# nfc-epd-power.net
KiCad netlist of a schematic drawn in Altium Designer
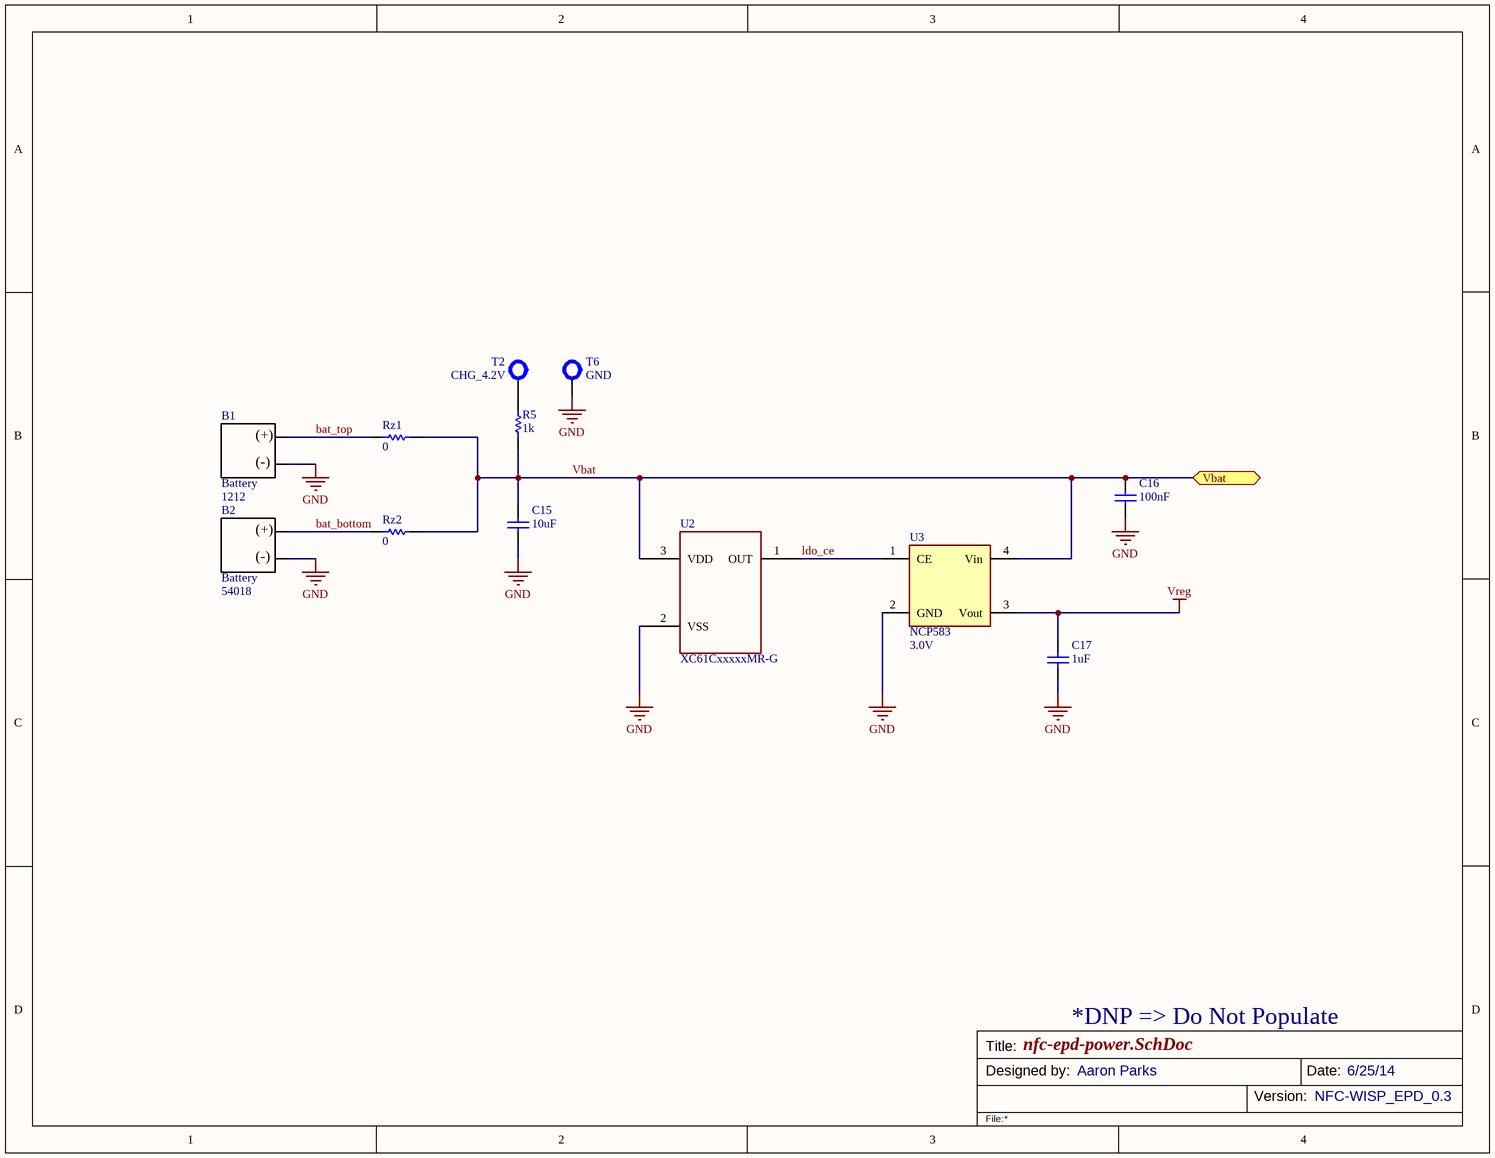
[diagram p0: nfc-epd-power.SchDoc]

(export (version "E")
  (design (tool "Eeschema 10.0.6"))
  (components
    (comp (ref "B1")
      (value "Battery")
      (footprint "PGEB0121212")
      (description "Powerstream Lithium Battery")
      (fields (field (name "NOTE") "1212"))
      (libsource (lib "powerstream") (part "Powerstream_Battery"))
    )
    (comp (ref "B2")
      (value "Battery")
      (footprint "PGEB0054018")
      (description "Powerstream Lithium Battery")
      (fields (field (name "NOTE") "54018"))
      (libsource (lib "powerstream") (part "Powerstream_Battery"))
    )
    (comp (ref "C15")
      (value "10uF")
      (footprint "0603")
      (description "Ceramic Capacitor (Surface Mount)")
      (fields (field (name "MANUFACTURER") "Generic Ceramic Chip Cap (TBD)") (field (name "Comment") "Cap"))
      (libsource (lib "WISP_AD10") (part "Cap"))
    )
    (comp (ref "C16")
      (value "100nF")
      (footprint "0402")
      (description "Ceramic Capacitor (Surface Mount)")
      (fields (field (name "MANUFACTURER") "Generic Ceramic Chip Cap (TBD)") (field (name "Comment") "Cap"))
      (libsource (lib "WISP_AD10") (part "Cap"))
    )
    (comp (ref "C17")
      (value "1uF")
      (footprint "0402")
      (description "Ceramic Capacitor (Surface Mount)")
      (fields (field (name "MANUFACTURER") "Generic Ceramic Chip Cap (TBD)") (field (name "Comment") "Cap"))
      (libsource (lib "WISP_AD10") (part "Cap"))
    )
    (comp (ref "R5")
      (value "1k")
      (footprint "0402")
      (description "Chip Resistor (Surface Mount)")
      (fields (field (name "MANUFACTURER") "Generic Chip Res (TBD)") (field (name "Comment") "Res"))
      (libsource (lib "WISP_AD10") (part "Res"))
    )
    (comp (ref "Rz1")
      (value "0")
      (footprint "0402")
      (description "Chip Resistor (Surface Mount)")
      (fields (field (name "MANUFACTURER") "Generic Chip Res (TBD)") (field (name "Comment") "Res"))
      (libsource (lib "WISP_AD10") (part "Res"))
    )
    (comp (ref "Rz2")
      (value "0")
      (footprint "0402")
      (description "Chip Resistor (Surface Mount)")
      (fields (field (name "MANUFACTURER") "Generic Chip Res (TBD)") (field (name "Comment") "Res"))
      (libsource (lib "WISP_AD10") (part "Res"))
    )
    (comp (ref "T2")
      (value "Test Point")
      (footprint "Test Point - Small")
      (description "Test Point, large or small foot prints")
      (fields
        (field (name "DIGI-KEY PART NUMBER") "Example: 5000K-ND, 5012K-ND, Surface mount 5015KCT-ND")
        (field (name "MANUFACTURER PART NUMBER") "Example: 5000, 5013")
        (field (name "NOTE") "CHG_4.2V")
      )
      (libsource (lib "WISP_AD10") (part "Test Point"))
    )
    (comp (ref "T6")
      (value "Test Point")
      (footprint "Test Point - Small")
      (description "Test Point, large or small foot prints")
      (fields
        (field (name "DIGI-KEY PART NUMBER") "Example: 5000K-ND, 5012K-ND, Surface mount 5015KCT-ND")
        (field (name "MANUFACTURER PART NUMBER") "Example: 5000, 5013")
        (field (name "NOTE") "GND")
      )
      (libsource (lib "WISP_AD10") (part "Test Point"))
    )
    (comp (ref "U2")
      (value "XC61CxxxxxMR-G")
      (footprint "SOT23 - N")
      (description "Torex IC Supervisor, SOT-23")
      (libsource (lib "WISP_AD10") (part "XC61CxxxxxMR-G"))
    )
    (comp (ref "U3")
      (value "NCP583")
      (footprint "SC82-AB")
      (description "Regulator: Ultra-Low Iq 150mA CMOS LDO Regulator with Enable")
      (fields
        (field (name "DIGI-KEY PART NUMBER") "NCP583SQ18T1GOSCT-ND")
        (field (name "MANUFACTURER") "ON Semiconductor")
        (field (name "ALTIUM_VALUE") "3.0V")
      )
      (libsource (lib "WISP_AD10") (part "NCP583"))
    )
  )
  (nets
    (net (code "1") (name "/Vbat") (class "Default")
      (node (ref "C15") (pin "2") (pinfunction "2_2") (pintype "passive"))
      (node (ref "C16") (pin "2") (pinfunction "2_2") (pintype "passive"))
      (node (ref "R5") (pin "1") (pinfunction "1_1") (pintype "passive"))
      (node (ref "Rz1") (pin "1") (pinfunction "1_1") (pintype "passive"))
      (node (ref "Rz2") (pin "1") (pinfunction "1_1") (pintype "passive"))
      (node (ref "U2") (pin "3") (pinfunction "VDD_3") (pintype "passive"))
      (node (ref "U3") (pin "4") (pinfunction "Vin_4") (pintype "passive"))
    )
    (net (code "2") (name "/bat_bottom") (class "Default")
      (node (ref "B2") (pin "2") (pinfunction "BAT_POS_2") (pintype "passive"))
      (node (ref "Rz2") (pin "2") (pinfunction "2_2") (pintype "passive"))
    )
    (net (code "3") (name "/bat_top") (class "Default")
      (node (ref "B1") (pin "2") (pinfunction "BAT_POS_2") (pintype "passive"))
      (node (ref "Rz1") (pin "2") (pinfunction "2_2") (pintype "passive"))
    )
    (net (code "4") (name "/ldo_ce") (class "Default")
      (node (ref "U2") (pin "1") (pinfunction "OUT_1") (pintype "passive"))
      (node (ref "U3") (pin "1") (pinfunction "CE_1") (pintype "passive"))
    )
    (net (code "5") (name "GND") (class "Default")
      (node (ref "B1") (pin "1") (pinfunction "BAT_NEG_1") (pintype "passive"))
      (node (ref "B2") (pin "1") (pinfunction "BAT_NEG_1") (pintype "passive"))
      (node (ref "C15") (pin "1") (pinfunction "1_1") (pintype "passive"))
      (node (ref "C16") (pin "1") (pinfunction "1_1") (pintype "passive"))
      (node (ref "C17") (pin "1") (pinfunction "1_1") (pintype "passive"))
      (node (ref "T6") (pin "0") (pinfunction "0_0") (pintype "passive"))
      (node (ref "U2") (pin "2") (pinfunction "VSS_2") (pintype "passive"))
      (node (ref "U3") (pin "2") (pinfunction "GND_2") (pintype "passive"))
    )
    (net (code "6") (name "Net-(R5-Pad2)") (class "Default")
      (node (ref "R5") (pin "2") (pinfunction "2_2") (pintype "passive"))
      (node (ref "T2") (pin "0") (pinfunction "0_0") (pintype "passive"))
    )
    (net (code "7") (name "Vreg") (class "Default")
      (node (ref "C17") (pin "2") (pinfunction "2_2") (pintype "passive"))
      (node (ref "U3") (pin "3") (pinfunction "Vout_3") (pintype "passive"))
    )
  )
)
